# LoraNode.net
KiCad netlist of a schematic drawn in Altium Designer
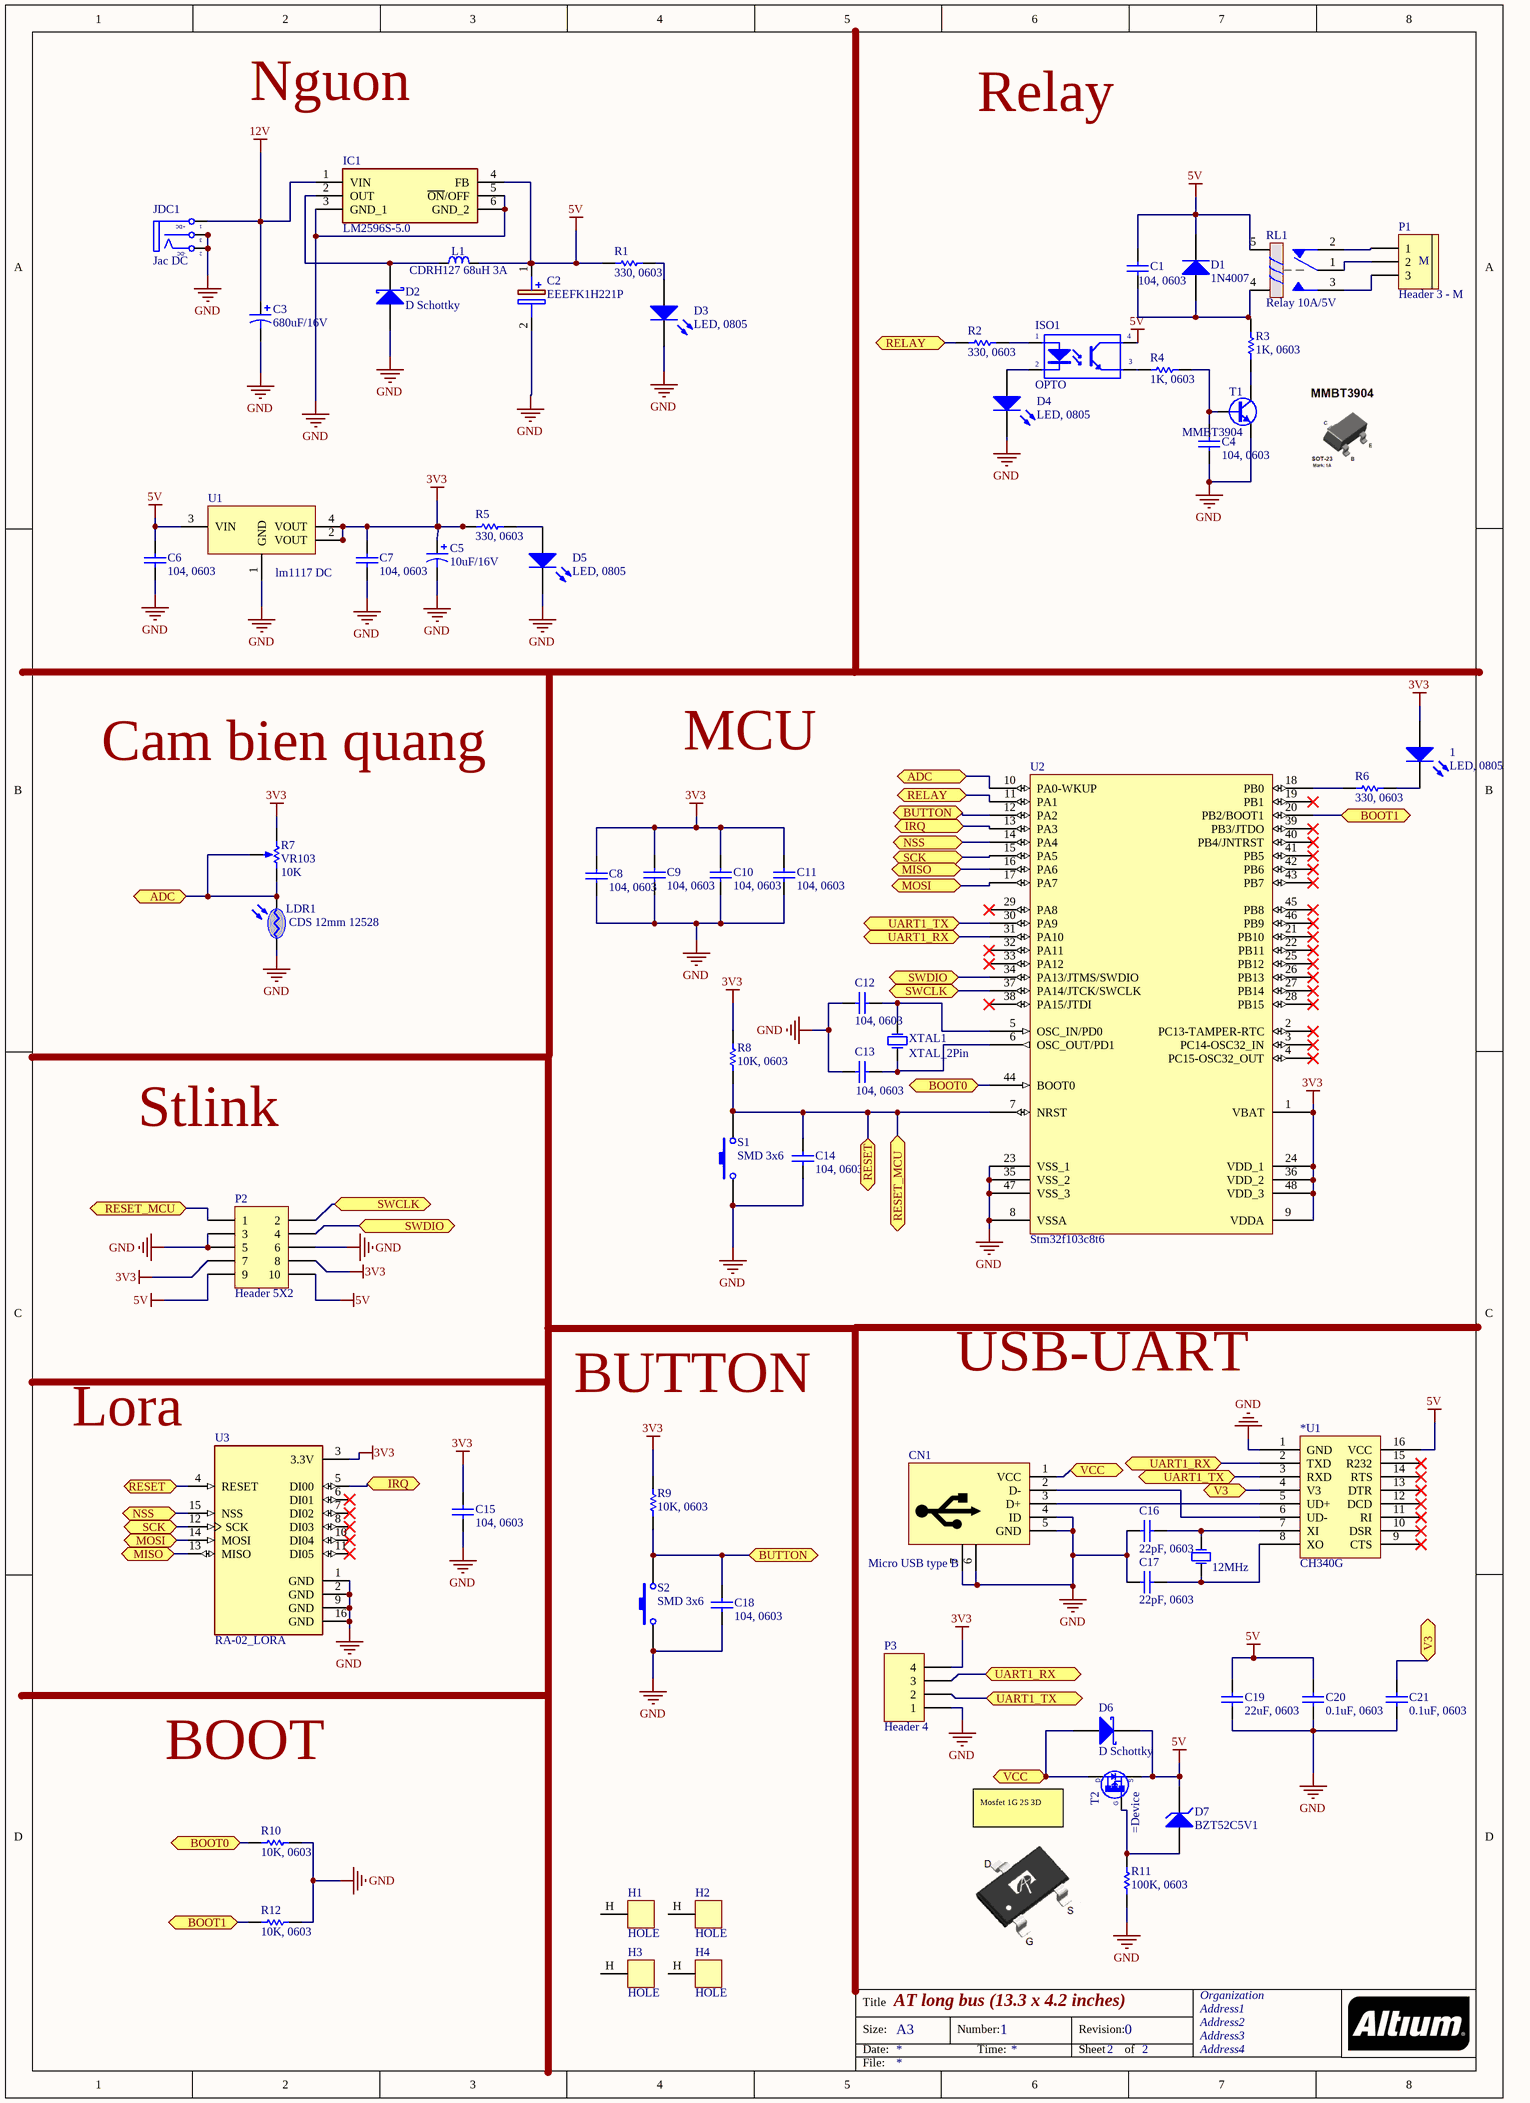
[diagram p0: LoraNode.schdoc]

(export (version "E")
  (design (tool "Eeschema 10.0.6"))
  (components
    (comp (ref "*U1")
      (value "CH340G")
      (footprint "SOIC127P680X230-16N")
      (libsource (lib "MinhLib") (part "CH340G"))
    )
    (comp (ref "1")
      (value "LED, 0805")
      (footprint "LED0805")
      (description "Typical INFRARED GaAs LED")
      (fields (field (name "PUBLISHER") "Altium Limited"))
      (libsource (lib "DoHuong_sch") (part "LED"))
    )
    (comp (ref "C1")
      (value "104, 0603")
      (footprint "0603 CAP")
      (description "Capacitor")
      (fields (field (name "Comment") "Cap") (field (name "PUBLISHER") "Altium Limited"))
      (libsource (lib "DoHuong_sch") (part "Cap"))
    )
    (comp (ref "C2")
      (value "EEEFK1H221P")
      (footprint "SamacSys:CAPAE1030X1080N")
      (description "Capacitor Polarised")
      (libsource (lib "*") (part "EEEFK1H221P"))
    )
    (comp (ref "C3")
      (value "680uF/16V")
      (footprint "Cap SMD 10x10x10,5")
      (description "Polarized Capacitor (Axial)")
      (fields (field (name "Comment") "Cap Pol2") (field (name "PUBLISHER") "Altium Limited"))
      (libsource (lib "DoHuong_sch") (part "Cap Pol2"))
    )
    (comp (ref "C4")
      (value "104, 0603")
      (footprint "0603 CAP")
      (description "Capacitor")
      (fields (field (name "Comment") "Cap") (field (name "PUBLISHER") "Altium Limited"))
      (libsource (lib "DoHuong_sch") (part "Cap"))
    )
    (comp (ref "C5")
      (value "10uF/16V")
      (footprint "Cap size B")
      (description "Polarized Capacitor (Axial)")
      (fields (field (name "Comment") "Cap Pol2") (field (name "PUBLISHER") "Altium Limited"))
      (libsource (lib "DoHuong_sch") (part "Cap Pol2"))
    )
    (comp (ref "C6")
      (value "104, 0603")
      (footprint "0603 CAP")
      (description "Capacitor")
      (fields (field (name "Comment") "Cap") (field (name "PUBLISHER") "Altium Limited"))
      (libsource (lib "DoHuong_sch") (part "Cap"))
    )
    (comp (ref "C7")
      (value "104, 0603")
      (footprint "0603 CAP")
      (description "Capacitor")
      (fields (field (name "Comment") "Cap") (field (name "PUBLISHER") "Altium Limited"))
      (libsource (lib "DoHuong_sch") (part "Cap"))
    )
    (comp (ref "C8")
      (value "104, 0603")
      (footprint "0603 CAP")
      (description "Capacitor")
      (fields (field (name "Comment") "Cap") (field (name "PUBLISHER") "Altium Limited"))
      (libsource (lib "DoHuong_sch") (part "Cap"))
    )
    (comp (ref "C9")
      (value "104, 0603")
      (footprint "0603 CAP")
      (description "Capacitor")
      (fields (field (name "Comment") "Cap") (field (name "PUBLISHER") "Altium Limited"))
      (libsource (lib "DoHuong_sch") (part "Cap"))
    )
    (comp (ref "C10")
      (value "104, 0603")
      (footprint "0603 CAP")
      (description "Capacitor")
      (fields (field (name "Comment") "Cap") (field (name "PUBLISHER") "Altium Limited"))
      (libsource (lib "DoHuong_sch") (part "Cap"))
    )
    (comp (ref "C11")
      (value "104, 0603")
      (footprint "0603 CAP")
      (description "Capacitor")
      (fields (field (name "Comment") "Cap") (field (name "PUBLISHER") "Altium Limited"))
      (libsource (lib "DoHuong_sch") (part "Cap"))
    )
    (comp (ref "C12")
      (value "104, 0603")
      (footprint "0603 CAP")
      (description "Capacitor")
      (fields (field (name "Comment") "Cap") (field (name "PUBLISHER") "Altium Limited"))
      (libsource (lib "DoHuong_sch") (part "Cap"))
    )
    (comp (ref "C13")
      (value "104, 0603")
      (footprint "0603 CAP")
      (description "Capacitor")
      (fields (field (name "Comment") "Cap") (field (name "PUBLISHER") "Altium Limited"))
      (libsource (lib "DoHuong_sch") (part "Cap"))
    )
    (comp (ref "C14")
      (value "104, 0603")
      (footprint "0603 CAP")
      (description "Capacitor")
      (fields (field (name "Comment") "Cap") (field (name "PUBLISHER") "Altium Limited"))
      (libsource (lib "DoHuong_sch") (part "Cap"))
    )
    (comp (ref "C15")
      (value "104, 0603")
      (footprint "0603 CAP")
      (description "Capacitor")
      (fields (field (name "Comment") "Cap") (field (name "PUBLISHER") "Altium Limited"))
      (libsource (lib "DoHuong_sch") (part "Cap"))
    )
    (comp (ref "C16")
      (value "22pF, 0603")
      (footprint "0603 CAP")
      (description "Capacitor")
      (fields (field (name "Comment") "Cap") (field (name "PUBLISHER") "Altium Limited"))
      (libsource (lib "DoHuong_sch") (part "Cap"))
    )
    (comp (ref "C17")
      (value "22pF, 0603")
      (footprint "0603 CAP")
      (description "Capacitor")
      (fields (field (name "Comment") "Cap") (field (name "PUBLISHER") "Altium Limited"))
      (libsource (lib "DoHuong_sch") (part "Cap"))
    )
    (comp (ref "C18")
      (value "104, 0603")
      (footprint "0603 CAP")
      (description "Capacitor")
      (fields (field (name "Comment") "Cap") (field (name "PUBLISHER") "Altium Limited"))
      (libsource (lib "DoHuong_sch") (part "Cap"))
    )
    (comp (ref "C19")
      (value "22uF, 0603")
      (footprint "0603 CAP")
      (description "Capacitor")
      (fields (field (name "Comment") "Cap") (field (name "PUBLISHER") "Altium Limited"))
      (libsource (lib "DoHuong_sch") (part "Cap"))
    )
    (comp (ref "C20")
      (value "0.1uF, 0603")
      (footprint "0603 CAP")
      (description "Capacitor")
      (fields (field (name "Comment") "Cap") (field (name "PUBLISHER") "Altium Limited"))
      (libsource (lib "DoHuong_sch") (part "Cap"))
    )
    (comp (ref "C21")
      (value "0.1uF, 0603")
      (footprint "0603 CAP")
      (description "Capacitor")
      (fields (field (name "Comment") "Cap") (field (name "PUBLISHER") "Altium Limited"))
      (libsource (lib "DoHuong_sch") (part "Cap"))
    )
    (comp (ref "CN1")
      (value "Micro USB type B")
      (footprint "USB-B-Micro-Hole")
      (libsource (lib "DoHuong_sch") (part "USB_MICRO_TYPE_B"))
    )
    (comp (ref "D1")
      (value "1N4007")
      (footprint "DO 214")
      (description "Default Diode")
      (fields (field (name "PUBLISHER") "Altium Limited"))
      (libsource (lib "DoHuong_sch") (part "Diode"))
    )
    (comp (ref "D2")
      (value "D Schottky")
      (footprint "DO-214AC")
      (description "Schottky Diode")
      (fields (field (name "PUBLISHER") "Altium Limited"))
      (libsource (lib "DoHuong_sch") (part "D Schottky"))
    )
    (comp (ref "D3")
      (value "LED, 0805")
      (footprint "LED0805")
      (description "Typical INFRARED GaAs LED")
      (fields (field (name "PUBLISHER") "Altium Limited"))
      (libsource (lib "DoHuong_sch") (part "LED"))
    )
    (comp (ref "D4")
      (value "LED, 0805")
      (footprint "LED0805")
      (description "Typical INFRARED GaAs LED")
      (fields (field (name "PUBLISHER") "Altium Limited"))
      (libsource (lib "DoHuong_sch") (part "LED"))
    )
    (comp (ref "D5")
      (value "LED, 0805")
      (footprint "LED0805")
      (description "Typical INFRARED GaAs LED")
      (fields (field (name "PUBLISHER") "Altium Limited"))
      (libsource (lib "DoHuong_sch") (part "LED"))
    )
    (comp (ref "D6")
      (value "D Schottky")
      (footprint "DO-214AC")
      (description "Schottky Diode")
      (fields (field (name "PUBLISHER") "Altium Limited"))
      (libsource (lib "DoHuong_sch") (part "D Schottky"))
    )
    (comp (ref "D7")
      (value "BZT52C5V1")
      (footprint "DO 214")
      (description "Zener Diode")
      (fields (field (name "PUBLISHER") "Altium Limited"))
      (libsource (lib "DoHuong_sch") (part "Diode Zener"))
    )
    (comp (ref "H1") (value "HOLE") (footprint "HOLE") (libsource (lib "ThinhNguyenLib") (part "HOLE")))
    (comp (ref "H2") (value "HOLE") (footprint "HOLE") (libsource (lib "ThinhNguyenLib") (part "HOLE")))
    (comp (ref "H3") (value "HOLE") (footprint "HOLE") (libsource (lib "ThinhNguyenLib") (part "HOLE")))
    (comp (ref "H4") (value "HOLE") (footprint "HOLE") (libsource (lib "ThinhNguyenLib") (part "HOLE")))
    (comp (ref "IC1")
      (value "LM2596S-5.0")
      (footprint "SamacSys:KTT0005B")
      (description "Integrated Circuit")
      (fields (field (name "MOUSER PART NUMBER") "926-LM2596S-50"))
      (libsource (lib "*") (part "LM2596S-5.0"))
    )
    (comp (ref "ISO1")
      (value "OPTO")
      (footprint "PC817 SMD")
      (libsource (lib "ThinhNguyenLib") (part "OPTO"))
    )
    (comp (ref "JDC1")
      (value "Jac DC")
      (footprint "DC-IN")
      (description "Jac DC input")
      (libsource (lib "DoHuong_sch") (part "DCIN"))
    )
    (comp (ref "L1")
      (value "CDRH127 68uH 3A")
      (footprint "IND_BOURNS_SRR1260")
      (description "Inductor")
      (libsource (lib "DoHuong_sch") (part "Inductor"))
    )
    (comp (ref "LDR1")
      (value "CDS 12mm 12528")
      (footprint "CDS")
      (description "Quang Tro")
      (libsource (lib "syhaunguyen") (part "LDR"))
    )
    (comp (ref "P1")
      (value "Header 3 - M")
      (footprint "Medium - Header 3")
      (description "Header, 3-Pin, Medium")
      (fields (field (name "PUBLISHER") "Altium Limited"))
      (libsource (lib "DoHuong_sch") (part "Header 3 - M"))
    )
    (comp (ref "P2")
      (value "Header 5X2")
      (footprint "HDR2X5")
      (description "Header, 5-Pin, Dual row")
      (fields (field (name "PUBLISHER") "Altium Limited"))
      (libsource (lib "DoHuong_sch") (part "Header 5X2"))
    )
    (comp (ref "P3")
      (value "Header 4")
      (footprint "HDR1X4")
      (description "Header, 4-Pin")
      (fields (field (name "PUBLISHER") "Altium Limited"))
      (libsource (lib "DoHuong_sch") (part "Header 4"))
    )
    (comp (ref "R1")
      (value "330, 0603")
      (footprint "0603 RESISTOR")
      (description "Semiconductor Resistor")
      (fields (field (name "Comment") "Resistor") (field (name "PUBLISHER") "Altium Limited"))
      (libsource (lib "DoHuong_sch") (part "Resistor"))
    )
    (comp (ref "R2")
      (value "330, 0603")
      (footprint "0603 RESISTOR")
      (description "Semiconductor Resistor")
      (fields (field (name "Comment") "Resistor") (field (name "PUBLISHER") "Altium Limited"))
      (libsource (lib "DoHuong_sch") (part "Resistor"))
    )
    (comp (ref "R3")
      (value "1K, 0603")
      (footprint "0603 RESISTOR")
      (description "Semiconductor Resistor")
      (fields (field (name "Comment") "Resistor") (field (name "PUBLISHER") "Altium Limited"))
      (libsource (lib "DoHuong_sch") (part "Resistor"))
    )
    (comp (ref "R4")
      (value "1K, 0603")
      (footprint "0603 RESISTOR")
      (description "Semiconductor Resistor")
      (fields (field (name "Comment") "Resistor") (field (name "PUBLISHER") "Altium Limited"))
      (libsource (lib "DoHuong_sch") (part "Resistor"))
    )
    (comp (ref "R5")
      (value "330, 0603")
      (footprint "0603 RESISTOR")
      (description "Semiconductor Resistor")
      (fields (field (name "Comment") "Resistor") (field (name "PUBLISHER") "Altium Limited"))
      (libsource (lib "DoHuong_sch") (part "Resistor"))
    )
    (comp (ref "R6")
      (value "330, 0603")
      (footprint "0603 RESISTOR")
      (description "Semiconductor Resistor")
      (fields (field (name "Comment") "Resistor") (field (name "PUBLISHER") "Altium Limited"))
      (libsource (lib "DoHuong_sch") (part "Resistor"))
    )
    (comp (ref "R7")
      (value "VR103")
      (footprint "VR")
      (description "Potentiometer")
      (fields (field (name "ALTIUM_VALUE") "10K") (field (name "PUBLISHER") "Altium Limited"))
      (libsource (lib "DoHuong_sch") (part "RPot"))
    )
    (comp (ref "R8")
      (value "10K, 0603")
      (footprint "0603 RESISTOR")
      (description "Semiconductor Resistor")
      (fields (field (name "Comment") "Resistor") (field (name "PUBLISHER") "Altium Limited"))
      (libsource (lib "DoHuong_sch") (part "Resistor"))
    )
    (comp (ref "R9")
      (value "10K, 0603")
      (footprint "0603 RESISTOR")
      (description "Semiconductor Resistor")
      (fields (field (name "Comment") "Resistor") (field (name "PUBLISHER") "Altium Limited"))
      (libsource (lib "DoHuong_sch") (part "Resistor"))
    )
    (comp (ref "R10")
      (value "10K, 0603")
      (footprint "0603 RESISTOR")
      (description "Semiconductor Resistor")
      (fields (field (name "Comment") "Resistor") (field (name "PUBLISHER") "Altium Limited"))
      (libsource (lib "DoHuong_sch") (part "Resistor"))
    )
    (comp (ref "R11")
      (value "100K, 0603")
      (footprint "0603 RESISTOR")
      (description "Semiconductor Resistor")
      (fields (field (name "Comment") "Resistor") (field (name "PUBLISHER") "Altium Limited"))
      (libsource (lib "DoHuong_sch") (part "Resistor"))
    )
    (comp (ref "R12")
      (value "10K, 0603")
      (footprint "0603 RESISTOR")
      (description "Semiconductor Resistor")
      (fields (field (name "Comment") "Resistor") (field (name "PUBLISHER") "Altium Limited"))
      (libsource (lib "DoHuong_sch") (part "Resistor"))
    )
    (comp (ref "RL1")
      (value "Relay 10A/5V")
      (footprint "RL_SPDT_10A")
      (description "Relay SPDT,10A - 12VDC 5 Pin")
      (libsource (lib "syhaunguyen") (part "Relay 1"))
    )
    (comp (ref "S1")
      (value "SMD 3x6")
      (footprint "SW-SMD")
      (description "Switch")
      (fields (field (name "PUBLISHER") "Altium Limited"))
      (libsource (lib "DoHuong_sch") (part "SW-PB"))
    )
    (comp (ref "S2")
      (value "SMD 3x6")
      (footprint "SW-SMD")
      (description "Switch")
      (fields (field (name "PUBLISHER") "Altium Limited"))
      (libsource (lib "DoHuong_sch") (part "SW-PB"))
    )
    (comp (ref "T1")
      (value "MMBT3904")
      (footprint "SOT23 - 3PIN")
      (description "NPN Transistor, 1B 2E 3C")
      (libsource (lib "DoHuong_sch") (part "NPN B1 E2 C3"))
    )
    (comp (ref "T2")
      (value "~")
      (footprint "SOT23 - 3PIN")
      (description "P-CHANNEL MOSFET WITH DIODE")
      (libsource (lib "DoHuong_sch") (part "P-MOSFET-D 1G 2S 3D"))
    )
    (comp (ref "U1")
      (value "lm1117 DC")
      (footprint "SOT230P700X175-4N")
      (description "lm1117")
      (libsource (lib "DoHuong_sch") (part "lm1117"))
    )
    (comp (ref "U2")
      (value "Stm32f103c8t6")
      (footprint "LQFP 48 PIN")
      (libsource (lib "MinhLib") (part "Stm32f103c8t6"))
    )
    (comp (ref "U3")
      (value "RA-02_LORA")
      (footprint "MODULE_RA-02_LORA")
      (description "Ra-02 LoRa RF M5Stack Platform Evaluation Expansion Board")
      (fields (field (name "MP") "Ra-02 LoRa") (field (name "MF") "AI-Thinker"))
      (libsource (lib "RA-02_LORA") (part "RA-02_LORA"))
    )
    (comp (ref "XTAL1")
      (value "XTAL_2Pin")
      (footprint "XTAL_HC-49/U")
      (libsource (lib "MinhLib") (part "XTAL_2Pin"))
    )
    (comp (ref "Y1")
      (value "12MHz")
      (footprint "XTAL_CITIZEN_HCM49")
      (description "Crystal Oscillator")
      (fields (field (name "PUBLISHER") "Altium Limited"))
      (libsource (lib "DoHuong_sch") (part "XTAL"))
    )
  )
  (nets
    (net (code "1") (name "/ADC") (class "Default")
      (node (ref "LDR1") (pin "2") (pinfunction "K_2") (pintype "passive"))
      (node (ref "R7") (pin "2") (pinfunction "TAP_2") (pintype "passive"))
      (node (ref "R7") (pin "3") (pinfunction "BOT_3") (pintype "passive"))
      (node (ref "U2") (pin "10") (pinfunction "PA0-WKUP_10") (pintype "bidirectional"))
    )
    (net (code "2") (name "/BOOT0") (class "Default")
      (node (ref "R10") (pin "2") (pinfunction "2_2") (pintype "passive"))
      (node (ref "U2") (pin "44") (pinfunction "BOOT0_44") (pintype "input"))
    )
    (net (code "3") (name "/BOOT1") (class "Default")
      (node (ref "R12") (pin "2") (pinfunction "2_2") (pintype "passive"))
      (node (ref "U2") (pin "20") (pinfunction "PB2/BOOT1_20") (pintype "bidirectional"))
    )
    (net (code "4") (name "/BUTTON") (class "Default")
      (node (ref "C18") (pin "2") (pinfunction "2_2") (pintype "passive"))
      (node (ref "R9") (pin "1") (pinfunction "1_1") (pintype "passive"))
      (node (ref "S2") (pin "2") (pinfunction "2_2") (pintype "passive"))
      (node (ref "U2") (pin "12") (pinfunction "PA2_12") (pintype "bidirectional"))
    )
    (net (code "5") (name "/IRQ") (class "Default")
      (node (ref "U2") (pin "13") (pinfunction "PA3_13") (pintype "bidirectional"))
      (node (ref "U3") (pin "5") (pinfunction "DI00_5") (pintype "bidirectional"))
    )
    (net (code "6") (name "/MISO") (class "Default")
      (node (ref "U2") (pin "16") (pinfunction "PA6_16") (pintype "bidirectional"))
      (node (ref "U3") (pin "13") (pinfunction "MISO_13") (pintype "bidirectional"))
    )
    (net (code "7") (name "/MOSI") (class "Default")
      (node (ref "U2") (pin "17") (pinfunction "PA7_17") (pintype "bidirectional"))
      (node (ref "U3") (pin "14") (pinfunction "MOSI_14") (pintype "input"))
    )
    (net (code "8") (name "/NSS") (class "Default")
      (node (ref "U2") (pin "14") (pinfunction "PA4_14") (pintype "bidirectional"))
      (node (ref "U3") (pin "15") (pinfunction "NSS_15") (pintype "input"))
    )
    (net (code "9") (name "/RELAY") (class "Default")
      (node (ref "R2") (pin "2") (pinfunction "2_2") (pintype "passive"))
      (node (ref "U2") (pin "11") (pinfunction "PA1_11") (pintype "bidirectional"))
    )
    (net (code "10") (name "/RESET") (class "Default")
      (node (ref "C14") (pin "2") (pinfunction "2_2") (pintype "passive"))
      (node (ref "P2") (pin "1") (pinfunction "1_1") (pintype "passive"))
      (node (ref "R8") (pin "1") (pinfunction "1_1") (pintype "passive"))
      (node (ref "S1") (pin "2") (pinfunction "2_2") (pintype "passive"))
      (node (ref "U2") (pin "7") (pinfunction "NRST_7") (pintype "bidirectional"))
      (node (ref "U3") (pin "4") (pinfunction "RESET_4") (pintype "input"))
    )
    (net (code "11") (name "/SCK") (class "Default")
      (node (ref "U2") (pin "15") (pinfunction "PA5_15") (pintype "bidirectional"))
      (node (ref "U3") (pin "12") (pinfunction "SCK_12") (pintype "input"))
    )
    (net (code "12") (name "/SWCLK") (class "Default")
      (node (ref "P2") (pin "2") (pinfunction "2_2") (pintype "passive"))
      (node (ref "U2") (pin "37") (pinfunction "PA14/JTCK/SWCLK_37") (pintype "bidirectional"))
    )
    (net (code "13") (name "/SWDIO") (class "Default")
      (node (ref "P2") (pin "4") (pinfunction "4_4") (pintype "passive"))
      (node (ref "U2") (pin "34") (pinfunction "PA13/JTMS/SWDIO_34") (pintype "bidirectional"))
    )
    (net (code "14") (name "/UART1_RX") (class "Default")
      (node (ref "*U1") (pin "2") (pinfunction "TXD_2") (pintype "passive"))
      (node (ref "P3") (pin "3") (pinfunction "3_3") (pintype "passive"))
      (node (ref "U2") (pin "31") (pinfunction "PA10_31") (pintype "bidirectional"))
    )
    (net (code "15") (name "/UART1_TX") (class "Default")
      (node (ref "*U1") (pin "3") (pinfunction "RXD_3") (pintype "passive"))
      (node (ref "P3") (pin "2") (pinfunction "2_2") (pintype "passive"))
      (node (ref "U2") (pin "30") (pinfunction "PA9_30") (pintype "bidirectional"))
    )
    (net (code "16") (name "/V3") (class "Default")
      (node (ref "*U1") (pin "4") (pinfunction "V3_4") (pintype "passive"))
      (node (ref "C21") (pin "1") (pinfunction "1_1") (pintype "passive"))
    )
    (net (code "17") (name "/VCC") (class "Default")
      (node (ref "CN1") (pin "1") (pinfunction "VCC_1") (pintype "passive"))
      (node (ref "D6") (pin "1") (pinfunction "A_1") (pintype "passive"))
      (node (ref "T2") (pin "3") (pinfunction "D_3") (pintype "passive"))
    )
    (net (code "18") (name "3V3") (class "Default")
      (node (ref "1") (pin "1") (pinfunction "A_1") (pintype "passive"))
      (node (ref "C10") (pin "2") (pinfunction "2_2") (pintype "passive"))
      (node (ref "C11") (pin "2") (pinfunction "2_2") (pintype "passive"))
      (node (ref "C15") (pin "2") (pinfunction "2_2") (pintype "passive"))
      (node (ref "C5") (pin "1") (pinfunction "1_1") (pintype "passive"))
      (node (ref "C7") (pin "2") (pinfunction "2_2") (pintype "passive"))
      (node (ref "C8") (pin "2") (pinfunction "2_2") (pintype "passive"))
      (node (ref "C9") (pin "2") (pinfunction "2_2") (pintype "passive"))
      (node (ref "P2") (pin "7") (pinfunction "7_7") (pintype "passive"))
      (node (ref "P2") (pin "8") (pinfunction "8_8") (pintype "passive"))
      (node (ref "P3") (pin "4") (pinfunction "4_4") (pintype "passive"))
      (node (ref "R5") (pin "2") (pinfunction "2_2") (pintype "passive"))
      (node (ref "R7") (pin "1") (pinfunction "TOP_1") (pintype "passive"))
      (node (ref "R8") (pin "2") (pinfunction "2_2") (pintype "passive"))
      (node (ref "R9") (pin "2") (pinfunction "2_2") (pintype "passive"))
      (node (ref "U1") (pin "2") (pinfunction "VOUT_2") (pintype "passive"))
      (node (ref "U1") (pin "4") (pinfunction "VOUT_4") (pintype "passive"))
      (node (ref "U2") (pin "1") (pinfunction "VBAT_1") (pintype "power_in"))
      (node (ref "U2") (pin "24") (pinfunction "VDD_1_24") (pintype "power_in"))
      (node (ref "U2") (pin "36") (pinfunction "VDD_2_36") (pintype "power_in"))
      (node (ref "U2") (pin "48") (pinfunction "VDD_3_48") (pintype "power_in"))
      (node (ref "U2") (pin "9") (pinfunction "VDDA_9") (pintype "power_in"))
      (node (ref "U3") (pin "3") (pinfunction "3.3V_3") (pintype "power_in"))
    )
    (net (code "19") (name "5V") (class "Default")
      (node (ref "*U1") (pin "16") (pinfunction "VCC_16") (pintype "passive"))
      (node (ref "C1") (pin "2") (pinfunction "2_2") (pintype "passive"))
      (node (ref "C19") (pin "1") (pinfunction "1_1") (pintype "passive"))
      (node (ref "C2") (pin "1") (pinfunction "+_1") (pintype "passive"))
      (node (ref "C20") (pin "1") (pinfunction "1_1") (pintype "passive"))
      (node (ref "C6") (pin "2") (pinfunction "2_2") (pintype "passive"))
      (node (ref "D1") (pin "2") (pinfunction "K_2") (pintype "passive"))
      (node (ref "D6") (pin "2") (pinfunction "K_2") (pintype "passive"))
      (node (ref "D7") (pin "2") (pinfunction "K_2") (pintype "passive"))
      (node (ref "IC1") (pin "4") (pinfunction "FB_4") (pintype "passive"))
      (node (ref "ISO1") (pin "4") (pinfunction "C_4") (pintype "passive"))
      (node (ref "L1") (pin "2") (pinfunction "2_2") (pintype "passive"))
      (node (ref "P2") (pin "10") (pinfunction "10_10") (pintype "passive"))
      (node (ref "P2") (pin "9") (pinfunction "9_9") (pintype "passive"))
      (node (ref "R1") (pin "2") (pinfunction "2_2") (pintype "passive"))
      (node (ref "RL1") (pin "5") (pinfunction "5_5") (pintype "passive"))
      (node (ref "T2") (pin "2") (pinfunction "S_2") (pintype "passive"))
      (node (ref "U1") (pin "3") (pinfunction "VIN_3") (pintype "passive"))
    )
    (net (code "20") (name "12V") (class "Default")
      (node (ref "C3") (pin "1") (pinfunction "1_1") (pintype "passive"))
      (node (ref "IC1") (pin "1") (pinfunction "VIN_1") (pintype "passive"))
      (node (ref "JDC1") (pin "1") (pinfunction "T_1") (pintype "passive"))
    )
    (net (code "21") (name "GND") (class "Default")
      (node (ref "*U1") (pin "1") (pinfunction "GND_1") (pintype "passive"))
      (node (ref "C10") (pin "1") (pinfunction "1_1") (pintype "passive"))
      (node (ref "C11") (pin "1") (pinfunction "1_1") (pintype "passive"))
      (node (ref "C12") (pin "2") (pinfunction "2_2") (pintype "passive"))
      (node (ref "C13") (pin "2") (pinfunction "2_2") (pintype "passive"))
      (node (ref "C14") (pin "1") (pinfunction "1_1") (pintype "passive"))
      (node (ref "C15") (pin "1") (pinfunction "1_1") (pintype "passive"))
      (node (ref "C16") (pin "2") (pinfunction "2_2") (pintype "passive"))
      (node (ref "C17") (pin "2") (pinfunction "2_2") (pintype "passive"))
      (node (ref "C18") (pin "1") (pinfunction "1_1") (pintype "passive"))
      (node (ref "C19") (pin "2") (pinfunction "2_2") (pintype "passive"))
      (node (ref "C2") (pin "2") (pinfunction "-_2") (pintype "passive"))
      (node (ref "C20") (pin "2") (pinfunction "2_2") (pintype "passive"))
      (node (ref "C21") (pin "2") (pinfunction "2_2") (pintype "passive"))
      (node (ref "C3") (pin "2") (pinfunction "2_2") (pintype "passive"))
      (node (ref "C4") (pin "1") (pinfunction "1_1") (pintype "passive"))
      (node (ref "C5") (pin "2") (pinfunction "2_2") (pintype "passive"))
      (node (ref "C6") (pin "1") (pinfunction "1_1") (pintype "passive"))
      (node (ref "C7") (pin "1") (pinfunction "1_1") (pintype "passive"))
      (node (ref "C8") (pin "1") (pinfunction "1_1") (pintype "passive"))
      (node (ref "C9") (pin "1") (pinfunction "1_1") (pintype "passive"))
      (node (ref "CN1") (pin "4") (pinfunction "ID_4") (pintype "passive"))
      (node (ref "CN1") (pin "5") (pinfunction "GND_5") (pintype "passive"))
      (node (ref "CN1") (pin "6") (pinfunction "GND_6") (pintype "passive"))
      (node (ref "CN1") (pin "7") (pinfunction "GND_7") (pintype "power_in"))
      (node (ref "D2") (pin "1") (pinfunction "A_1") (pintype "passive"))
      (node (ref "D3") (pin "2") (pinfunction "K_2") (pintype "passive"))
      (node (ref "D4") (pin "2") (pinfunction "K_2") (pintype "passive"))
      (node (ref "D5") (pin "2") (pinfunction "K_2") (pintype "passive"))
      (node (ref "IC1") (pin "3") (pinfunction "GND_1_3") (pintype "passive"))
      (node (ref "IC1") (pin "5") (pinfunction "~{ON}/OFF_5") (pintype "passive"))
      (node (ref "IC1") (pin "6") (pinfunction "GND_2_6") (pintype "passive"))
      (node (ref "JDC1") (pin "2") (pinfunction "TN_2") (pintype "passive"))
      (node (ref "JDC1") (pin "3") (pinfunction "S_3") (pintype "power_in"))
      (node (ref "LDR1") (pin "1") (pinfunction "A_1") (pintype "passive"))
      (node (ref "P2") (pin "3") (pinfunction "3_3") (pintype "passive"))
      (node (ref "P2") (pin "5") (pinfunction "5_5") (pintype "passive"))
      (node (ref "P2") (pin "6") (pinfunction "6_6") (pintype "passive"))
      (node (ref "P3") (pin "1") (pinfunction "1_1") (pintype "passive"))
      (node (ref "R10") (pin "1") (pinfunction "1_1") (pintype "passive"))
      (node (ref "R11") (pin "2") (pinfunction "2_2") (pintype "passive"))
      (node (ref "R12") (pin "1") (pinfunction "1_1") (pintype "passive"))
      (node (ref "S1") (pin "1") (pinfunction "1_1") (pintype "passive"))
      (node (ref "S2") (pin "1") (pinfunction "1_1") (pintype "passive"))
      (node (ref "T1") (pin "2") (pinfunction "E_2") (pintype "passive"))
      (node (ref "U1") (pin "1") (pinfunction "GND_1") (pintype "passive"))
      (node (ref "U2") (pin "23") (pinfunction "VSS_1_23") (pintype "power_in"))
      (node (ref "U2") (pin "35") (pinfunction "VSS_2_35") (pintype "power_in"))
      (node (ref "U2") (pin "47") (pinfunction "VSS_3_47") (pintype "power_in"))
      (node (ref "U2") (pin "8") (pinfunction "VSSA_8") (pintype "power_in"))
      (node (ref "U3") (pin "1") (pinfunction "GND_1") (pintype "power_in"))
      (node (ref "U3") (pin "16") (pinfunction "GND_16") (pintype "power_in"))
      (node (ref "U3") (pin "2") (pinfunction "GND_2") (pintype "power_in"))
      (node (ref "U3") (pin "9") (pinfunction "GND_9") (pintype "power_in"))
    )
    (net (code "22") (name "Net-(*U1-UD+)") (class "Default")
      (node (ref "*U1") (pin "5") (pinfunction "UD+_5") (pintype "passive"))
      (node (ref "CN1") (pin "3") (pinfunction "D+_3") (pintype "passive"))
    )
    (net (code "23") (name "Net-(*U1-UD-)") (class "Default")
      (node (ref "*U1") (pin "6") (pinfunction "UD-_6") (pintype "passive"))
      (node (ref "CN1") (pin "2") (pinfunction "D-_2") (pintype "passive"))
    )
    (net (code "24") (name "Net-(*U1-XI)") (class "Default")
      (node (ref "*U1") (pin "7") (pinfunction "XI_7") (pintype "passive"))
      (node (ref "C16") (pin "1") (pinfunction "1_1") (pintype "passive"))
      (node (ref "Y1") (pin "2") (pinfunction "OSC2_2") (pintype "passive"))
    )
    (net (code "25") (name "Net-(*U1-XO)") (class "Default")
      (node (ref "*U1") (pin "8") (pinfunction "XO_8") (pintype "passive"))
      (node (ref "C17") (pin "1") (pinfunction "1_1") (pintype "passive"))
      (node (ref "Y1") (pin "1") (pinfunction "OSC1_1") (pintype "passive"))
    )
    (net (code "26") (name "Net-(1-K)") (class "Default")
      (node (ref "1") (pin "2") (pinfunction "K_2") (pintype "passive"))
      (node (ref "R6") (pin "2") (pinfunction "2_2") (pintype "passive"))
    )
    (net (code "27") (name "Net-(D1-A)") (class "Default")
      (node (ref "C1") (pin "1") (pinfunction "1_1") (pintype "passive"))
      (node (ref "D1") (pin "1") (pinfunction "A_1") (pintype "passive"))
      (node (ref "R3") (pin "1") (pinfunction "1_1") (pintype "passive"))
      (node (ref "RL1") (pin "4") (pinfunction "4_4") (pintype "passive"))
    )
    (net (code "28") (name "Net-(D2-K)") (class "Default")
      (node (ref "D2") (pin "2") (pinfunction "K_2") (pintype "passive"))
      (node (ref "IC1") (pin "2") (pinfunction "OUT_2") (pintype "passive"))
      (node (ref "L1") (pin "1") (pinfunction "1_1") (pintype "passive"))
    )
    (net (code "29") (name "Net-(D3-A)") (class "Default")
      (node (ref "D3") (pin "1") (pinfunction "A_1") (pintype "passive"))
      (node (ref "R1") (pin "1") (pinfunction "1_1") (pintype "passive"))
    )
    (net (code "30") (name "Net-(D4-A)") (class "Default")
      (node (ref "D4") (pin "1") (pinfunction "A_1") (pintype "passive"))
      (node (ref "ISO1") (pin "2") (pinfunction "K_2") (pintype "passive"))
    )
    (net (code "31") (name "Net-(D5-A)") (class "Default")
      (node (ref "D5") (pin "1") (pinfunction "A_1") (pintype "passive"))
      (node (ref "R5") (pin "1") (pinfunction "1_1") (pintype "passive"))
    )
    (net (code "32") (name "Net-(D7-A)") (class "Default")
      (node (ref "D7") (pin "1") (pinfunction "A_1") (pintype "passive"))
      (node (ref "R11") (pin "1") (pinfunction "1_1") (pintype "passive"))
      (node (ref "T2") (pin "1") (pinfunction "G_1") (pintype "passive"))
    )
    (net (code "33") (name "Net-(ISO1-A)") (class "Default")
      (node (ref "ISO1") (pin "1") (pinfunction "A_1") (pintype "passive"))
      (node (ref "R2") (pin "1") (pinfunction "1_1") (pintype "passive"))
    )
    (net (code "34") (name "Net-(ISO1-E)") (class "Default")
      (node (ref "ISO1") (pin "3") (pinfunction "E_3") (pintype "passive"))
      (node (ref "R4") (pin "2") (pinfunction "2_2") (pintype "passive"))
    )
    (net (code "35") (name "Net-(P1-Pad1)") (class "Default")
      (node (ref "P1") (pin "1") (pinfunction "1_1") (pintype "passive"))
      (node (ref "RL1") (pin "2") (pinfunction "2_2") (pintype "passive"))
    )
    (net (code "36") (name "Net-(P1-Pad2)") (class "Default")
      (node (ref "P1") (pin "2") (pinfunction "2_2") (pintype "passive"))
      (node (ref "RL1") (pin "1") (pinfunction "1_1") (pintype "passive"))
    )
    (net (code "37") (name "Net-(P1-Pad3)") (class "Default")
      (node (ref "P1") (pin "3") (pinfunction "3_3") (pintype "passive"))
      (node (ref "RL1") (pin "3") (pinfunction "3_3") (pintype "passive"))
    )
    (net (code "38") (name "Net-(T1-B)") (class "Default")
      (node (ref "C4") (pin "2") (pinfunction "2_2") (pintype "passive"))
      (node (ref "R4") (pin "1") (pinfunction "1_1") (pintype "passive"))
      (node (ref "T1") (pin "1") (pinfunction "B_1") (pintype "passive"))
    )
    (net (code "39") (name "Net-(T1-C)") (class "Default")
      (node (ref "R3") (pin "2") (pinfunction "2_2") (pintype "passive"))
      (node (ref "T1") (pin "3") (pinfunction "C_3") (pintype "passive"))
    )
    (net (code "40") (name "Net-(U2-OSC_IN{slash}PD0)") (class "Default")
      (node (ref "C12") (pin "1") (pinfunction "1_1") (pintype "passive"))
      (node (ref "U2") (pin "5") (pinfunction "OSC_IN/PD0_5") (pintype "input"))
      (node (ref "XTAL1") (pin "2") (pinfunction "OSC2_2") (pintype "passive"))
    )
    (net (code "41") (name "Net-(U2-OSC_OUT{slash}PD1)") (class "Default")
      (node (ref "C13") (pin "1") (pinfunction "1_1") (pintype "passive"))
      (node (ref "U2") (pin "6") (pinfunction "OSC_OUT/PD1_6") (pintype "output"))
      (node (ref "XTAL1") (pin "1") (pinfunction "OSC1_1") (pintype "passive"))
    )
    (net (code "42") (name "Net-(U2-PB0)") (class "Default")
      (node (ref "R6") (pin "1") (pinfunction "1_1") (pintype "passive"))
      (node (ref "U2") (pin "18") (pinfunction "PB0_18") (pintype "bidirectional"))
    )
    (net (code "43") (name "unconnected-(*U1-CTS-Pad9)") (class "Default")
      (node (ref "*U1") (pin "9") (pinfunction "CTS_9") (pintype "passive+no_connect"))
    )
    (net (code "44") (name "unconnected-(*U1-DCD-Pad12)") (class "Default")
      (node (ref "*U1") (pin "12") (pinfunction "DCD_12") (pintype "passive+no_connect"))
    )
    (net (code "45") (name "unconnected-(*U1-DSR-Pad10)") (class "Default")
      (node (ref "*U1") (pin "10") (pinfunction "DSR_10") (pintype "passive+no_connect"))
    )
    (net (code "46") (name "unconnected-(*U1-DTR-Pad13)") (class "Default")
      (node (ref "*U1") (pin "13") (pinfunction "DTR_13") (pintype "passive+no_connect"))
    )
    (net (code "47") (name "unconnected-(*U1-R232-Pad15)") (class "Default")
      (node (ref "*U1") (pin "15") (pinfunction "R232_15") (pintype "passive+no_connect"))
    )
    (net (code "48") (name "unconnected-(*U1-RI-Pad11)") (class "Default")
      (node (ref "*U1") (pin "11") (pinfunction "RI_11") (pintype "passive+no_connect"))
    )
    (net (code "49") (name "unconnected-(*U1-RTS-Pad14)") (class "Default")
      (node (ref "*U1") (pin "14") (pinfunction "RTS_14") (pintype "passive+no_connect"))
    )
    (net (code "50") (name "unconnected-(H1-HOLE-PadH)") (class "Default")
      (node (ref "H1") (pin "H") (pinfunction "HOLE_H") (pintype "passive"))
    )
    (net (code "51") (name "unconnected-(H2-HOLE-PadH)") (class "Default")
      (node (ref "H2") (pin "H") (pinfunction "HOLE_H") (pintype "passive"))
    )
    (net (code "52") (name "unconnected-(H3-HOLE-PadH)") (class "Default")
      (node (ref "H3") (pin "H") (pinfunction "HOLE_H") (pintype "passive"))
    )
    (net (code "53") (name "unconnected-(H4-HOLE-PadH)") (class "Default")
      (node (ref "H4") (pin "H") (pinfunction "HOLE_H") (pintype "passive"))
    )
    (net (code "54") (name "unconnected-(U2-PA8-Pad29)") (class "Default")
      (node (ref "U2") (pin "29") (pinfunction "PA8_29") (pintype "bidirectional+no_connect"))
    )
    (net (code "55") (name "unconnected-(U2-PA11-Pad32)") (class "Default")
      (node (ref "U2") (pin "32") (pinfunction "PA11_32") (pintype "bidirectional+no_connect"))
    )
    (net (code "56") (name "unconnected-(U2-PA12-Pad33)") (class "Default")
      (node (ref "U2") (pin "33") (pinfunction "PA12_33") (pintype "bidirectional+no_connect"))
    )
    (net (code "57") (name "unconnected-(U2-PA15{slash}JTDI-Pad38)") (class "Default")
      (node (ref "U2") (pin "38") (pinfunction "PA15/JTDI_38") (pintype "bidirectional+no_connect"))
    )
    (net (code "58") (name "unconnected-(U2-PB1-Pad19)") (class "Default")
      (node (ref "U2") (pin "19") (pinfunction "PB1_19") (pintype "bidirectional+no_connect"))
    )
    (net (code "59") (name "unconnected-(U2-PB3{slash}JTDO-Pad39)") (class "Default")
      (node (ref "U2") (pin "39") (pinfunction "PB3/JTDO_39") (pintype "bidirectional+no_connect"))
    )
    (net (code "60") (name "unconnected-(U2-PB4{slash}JNTRST-Pad40)") (class "Default")
      (node (ref "U2") (pin "40") (pinfunction "PB4/JNTRST_40") (pintype "bidirectional+no_connect"))
    )
    (net (code "61") (name "unconnected-(U2-PB5-Pad41)") (class "Default")
      (node (ref "U2") (pin "41") (pinfunction "PB5_41") (pintype "bidirectional+no_connect"))
    )
    (net (code "62") (name "unconnected-(U2-PB6-Pad42)") (class "Default")
      (node (ref "U2") (pin "42") (pinfunction "PB6_42") (pintype "bidirectional+no_connect"))
    )
    (net (code "63") (name "unconnected-(U2-PB7-Pad43)") (class "Default")
      (node (ref "U2") (pin "43") (pinfunction "PB7_43") (pintype "bidirectional+no_connect"))
    )
    (net (code "64") (name "unconnected-(U2-PB8-Pad45)") (class "Default")
      (node (ref "U2") (pin "45") (pinfunction "PB8_45") (pintype "bidirectional+no_connect"))
    )
    (net (code "65") (name "unconnected-(U2-PB9-Pad46)") (class "Default")
      (node (ref "U2") (pin "46") (pinfunction "PB9_46") (pintype "bidirectional+no_connect"))
    )
    (net (code "66") (name "unconnected-(U2-PB10-Pad21)") (class "Default")
      (node (ref "U2") (pin "21") (pinfunction "PB10_21") (pintype "bidirectional+no_connect"))
    )
    (net (code "67") (name "unconnected-(U2-PB11-Pad22)") (class "Default")
      (node (ref "U2") (pin "22") (pinfunction "PB11_22") (pintype "bidirectional+no_connect"))
    )
    (net (code "68") (name "unconnected-(U2-PB12-Pad25)") (class "Default")
      (node (ref "U2") (pin "25") (pinfunction "PB12_25") (pintype "bidirectional+no_connect"))
    )
    (net (code "69") (name "unconnected-(U2-PB13-Pad26)") (class "Default")
      (node (ref "U2") (pin "26") (pinfunction "PB13_26") (pintype "bidirectional+no_connect"))
    )
    (net (code "70") (name "unconnected-(U2-PB14-Pad27)") (class "Default")
      (node (ref "U2") (pin "27") (pinfunction "PB14_27") (pintype "bidirectional+no_connect"))
    )
    (net (code "71") (name "unconnected-(U2-PB15-Pad28)") (class "Default")
      (node (ref "U2") (pin "28") (pinfunction "PB15_28") (pintype "bidirectional+no_connect"))
    )
    (net (code "72") (name "unconnected-(U2-PC13-TAMPER-RTC-Pad2)") (class "Default")
      (node (ref "U2") (pin "2") (pinfunction "PC13-TAMPER-RTC_2") (pintype "bidirectional+no_connect"))
    )
    (net (code "73") (name "unconnected-(U2-PC14-OSC32_IN-Pad3)") (class "Default")
      (node (ref "U2") (pin "3") (pinfunction "PC14-OSC32_IN_3") (pintype "bidirectional+no_connect"))
    )
    (net (code "74") (name "unconnected-(U2-PC15-OSC32_OUT-Pad4)") (class "Default")
      (node (ref "U2") (pin "4") (pinfunction "PC15-OSC32_OUT_4") (pintype "bidirectional+no_connect"))
    )
    (net (code "75") (name "unconnected-(U3-DI01-Pad6)") (class "Default")
      (node (ref "U3") (pin "6") (pinfunction "DI01_6") (pintype "bidirectional+no_connect"))
    )
    (net (code "76") (name "unconnected-(U3-DI02-Pad7)") (class "Default")
      (node (ref "U3") (pin "7") (pinfunction "DI02_7") (pintype "bidirectional+no_connect"))
    )
    (net (code "77") (name "unconnected-(U3-DI03-Pad8)") (class "Default")
      (node (ref "U3") (pin "8") (pinfunction "DI03_8") (pintype "bidirectional+no_connect"))
    )
    (net (code "78") (name "unconnected-(U3-DI04-Pad10)") (class "Default")
      (node (ref "U3") (pin "10") (pinfunction "DI04_10") (pintype "bidirectional+no_connect"))
    )
    (net (code "79") (name "unconnected-(U3-DI05-Pad11)") (class "Default")
      (node (ref "U3") (pin "11") (pinfunction "DI05_11") (pintype "bidirectional+no_connect"))
    )
  )
)
